# COEXPIX_connectors_schematics.net
KiCad netlist of a schematic drawn in Altium Designer
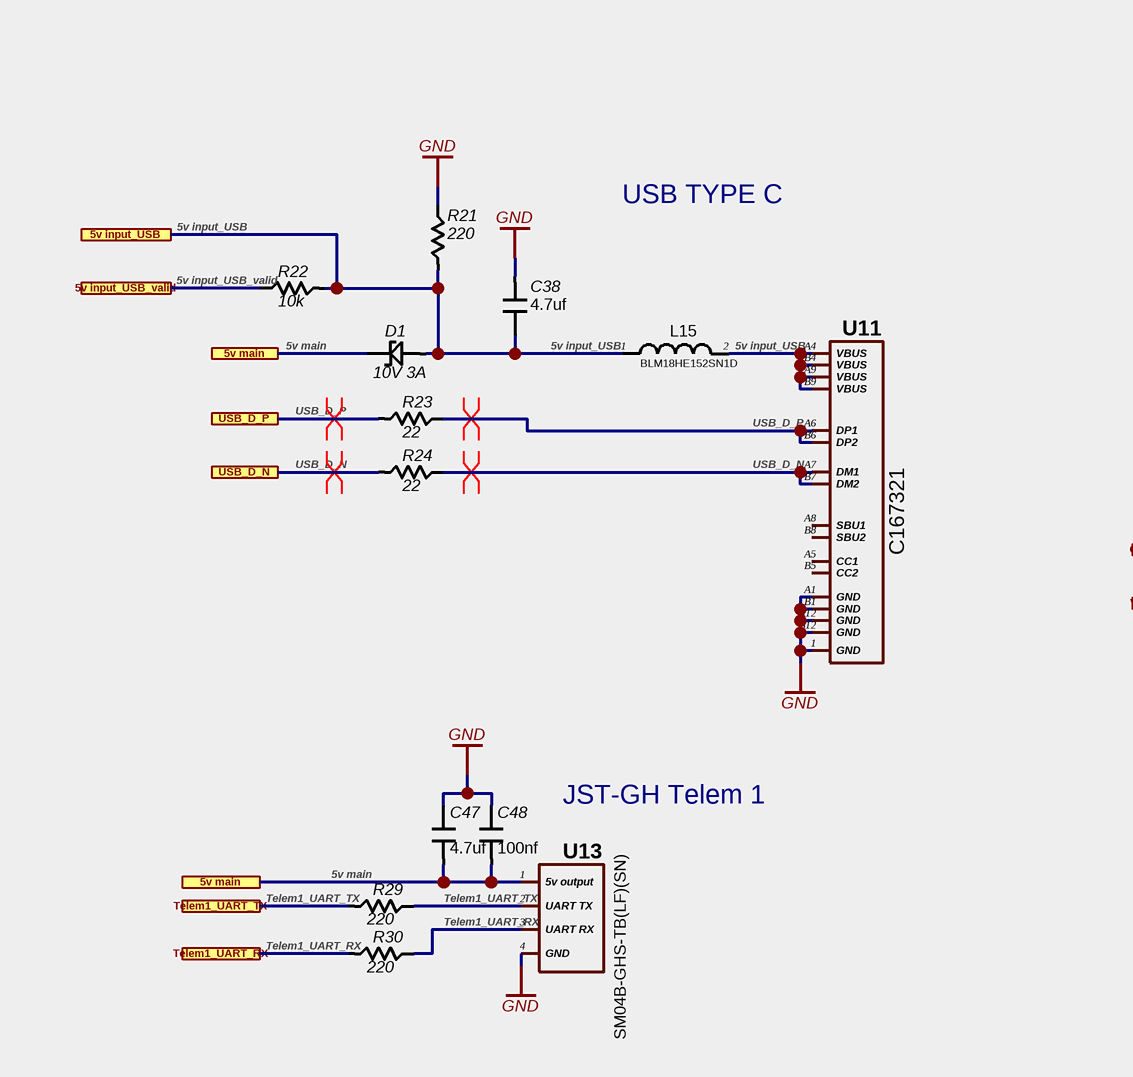
[diagram p0: COEXPIX connectors schematics.SchDoc, top left]
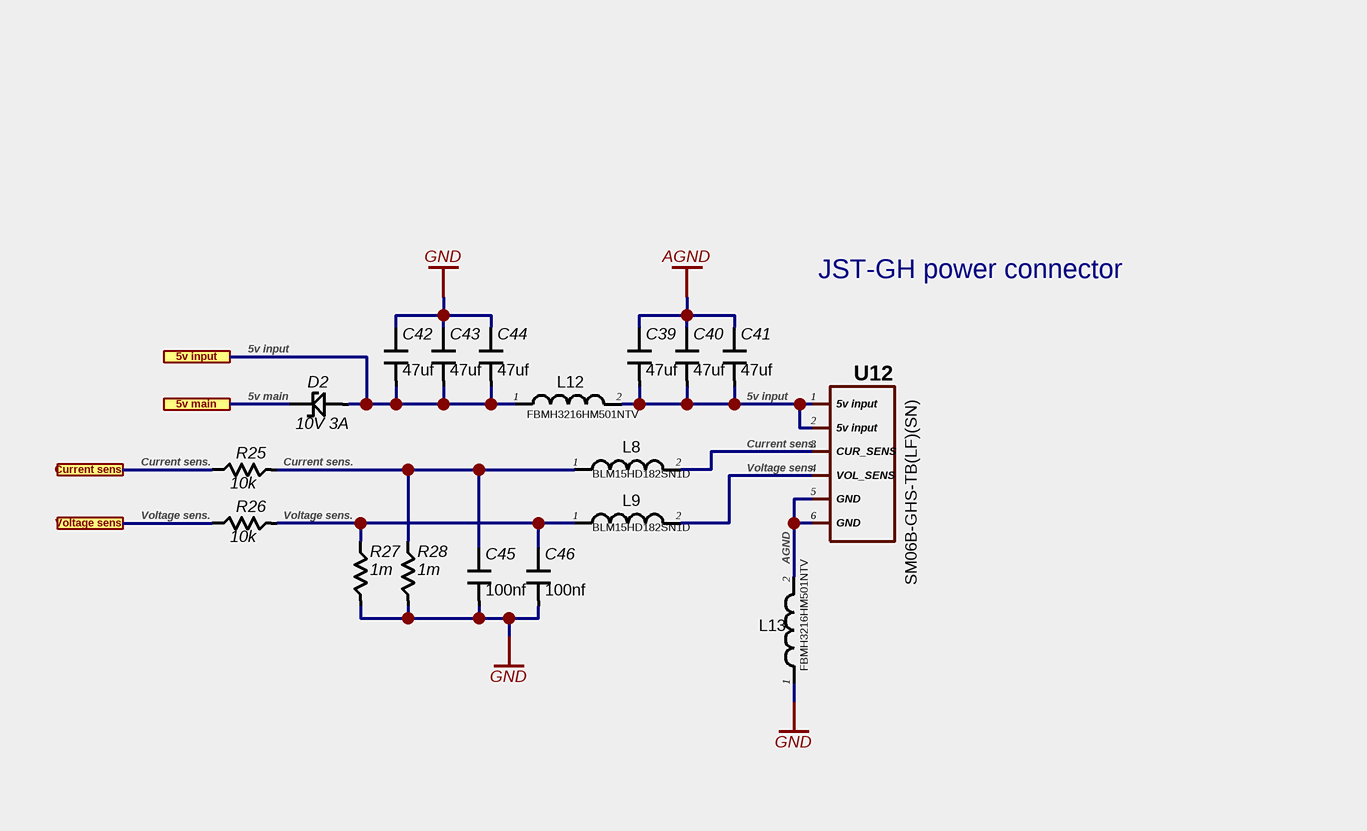
[diagram p1: COEXPIX connectors schematics.SchDoc, top right]
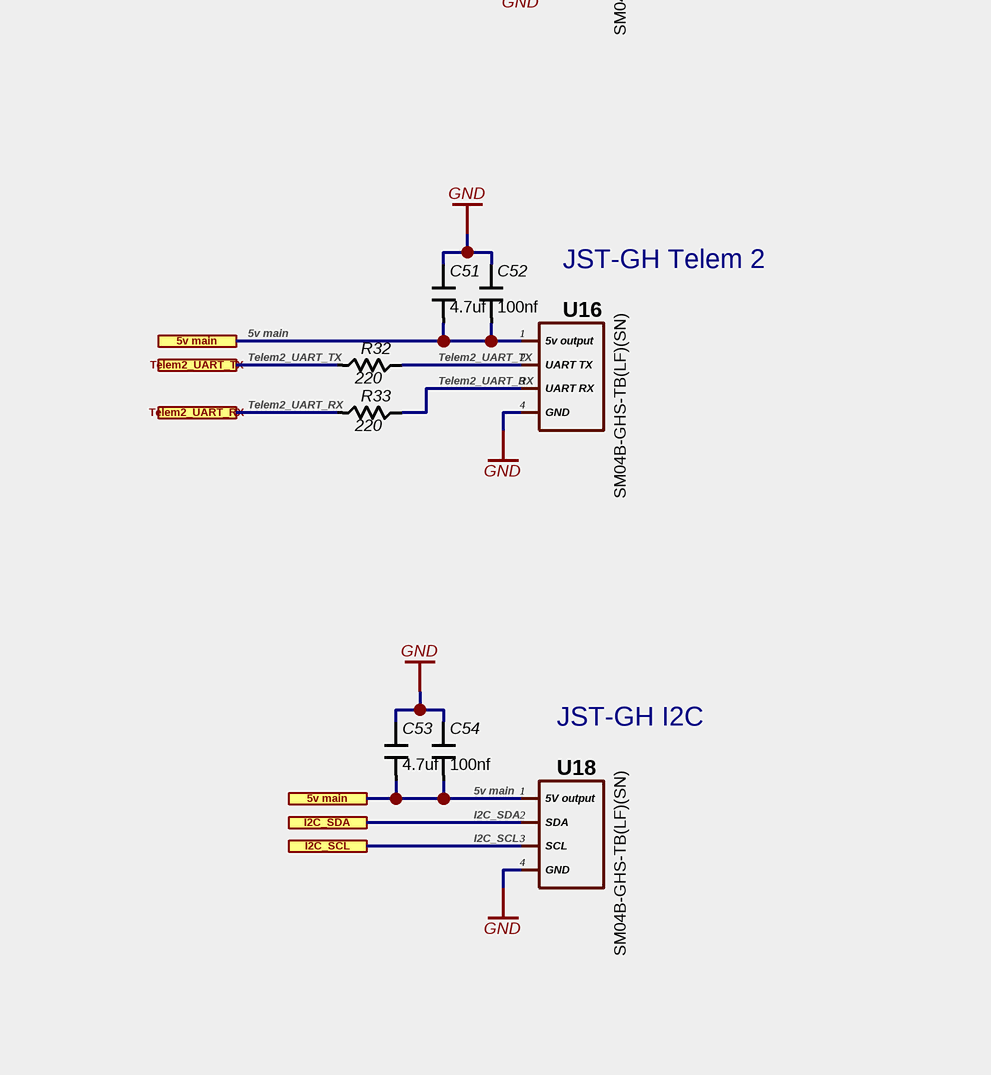
[diagram p2: COEXPIX connectors schematics.SchDoc, bottom left]
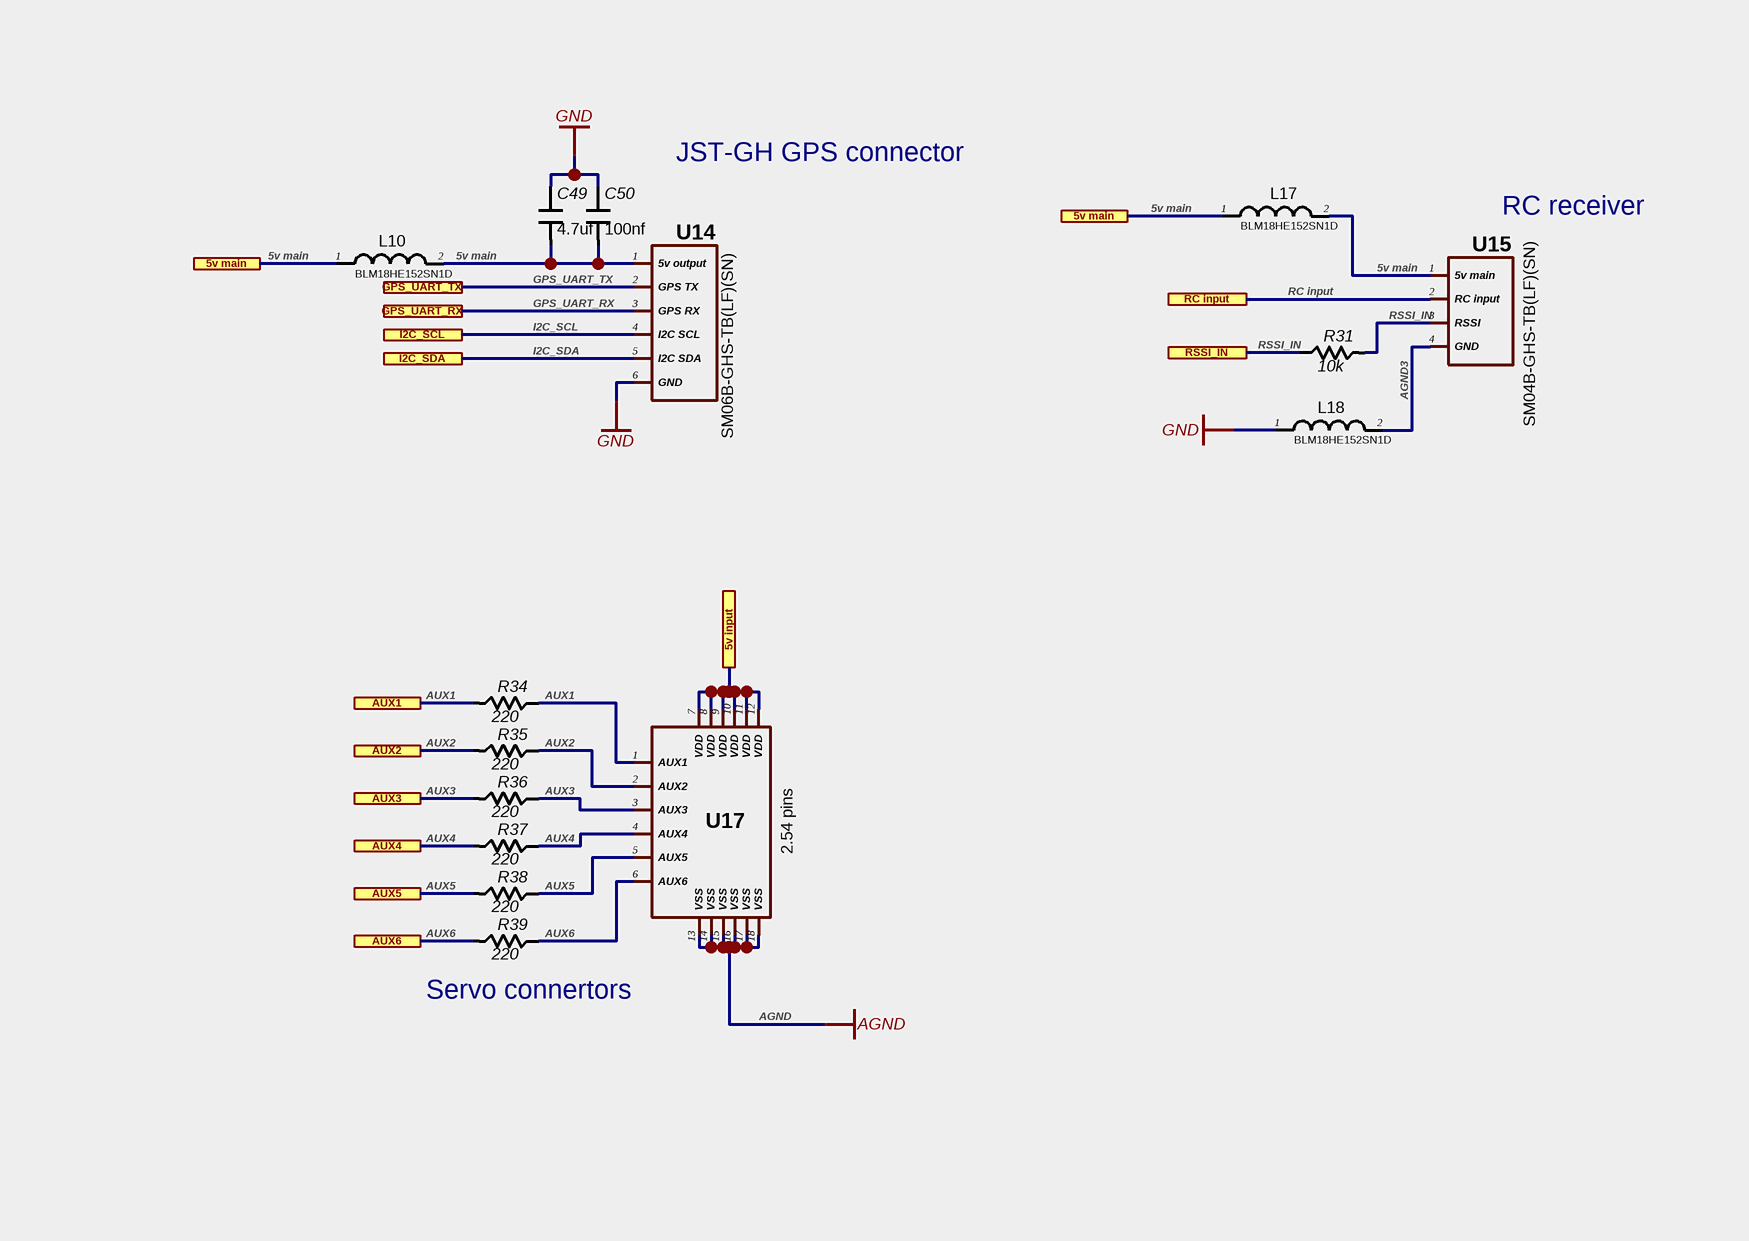
[diagram p3: COEXPIX connectors schematics.SchDoc, bottom right]

(export (version "E")
  (design (tool "Eeschema 10.0.6"))
  (components
    (comp (ref "C38")
      (value "4.7uf")
      (footprint "Capasitor 0402")
      (description "4.7uF ±20% 6.3V X5R 0402 Multilayer Ceramic Capacitor")
      (fields (field (name "PART NUMBER") "JMK105BBJ475MV-F") (field (name "MANUFACTURER") "Taiyo Yuden"))
      (libsource (lib "Schematic symbols library") (part "Capacitor MLCC"))
    )
    (comp (ref "C39")
      (value "47uf")
      (footprint "Capasitor 0603")
      (description "Multilayer Ceramic Capacitors MLCC - SMD/SMT 47uF 6.3V 0603")
      (fields (field (name "PART NUMBER") "GRM188R60J476ME15D") (field (name "MANUFACTURER") "Murata"))
      (libsource (lib "Schematic symbols library") (part "Capacitor MLCC"))
    )
    (comp (ref "C40")
      (value "47uf")
      (footprint "Capasitor 0603")
      (description "Multilayer Ceramic Capacitors MLCC - SMD/SMT 47uF 6.3V 0603")
      (fields (field (name "PART NUMBER") "GRM188R60J476ME15D") (field (name "MANUFACTURER") "Murata"))
      (libsource (lib "Schematic symbols library") (part "Capacitor MLCC"))
    )
    (comp (ref "C41")
      (value "47uf")
      (footprint "Capasitor 0603")
      (description "Multilayer Ceramic Capacitors MLCC - SMD/SMT 47uF 6.3V 0603")
      (fields (field (name "PART NUMBER") "GRM188R60J476ME15D") (field (name "MANUFACTURER") "Murata"))
      (libsource (lib "Schematic symbols library") (part "Capacitor MLCC"))
    )
    (comp (ref "C42")
      (value "47uf")
      (footprint "Capasitor 0603")
      (description "Multilayer Ceramic Capacitors MLCC - SMD/SMT 47uF 6.3V 0603")
      (fields (field (name "PART NUMBER") "GRM188R60J476ME15D") (field (name "MANUFACTURER") "Murata"))
      (libsource (lib "Schematic symbols library") (part "Capacitor MLCC"))
    )
    (comp (ref "C43")
      (value "47uf")
      (footprint "Capasitor 0603")
      (description "Multilayer Ceramic Capacitors MLCC - SMD/SMT 47uF 6.3V 0603")
      (fields (field (name "PART NUMBER") "GRM188R60J476ME15D") (field (name "MANUFACTURER") "Murata"))
      (libsource (lib "Schematic symbols library") (part "Capacitor MLCC"))
    )
    (comp (ref "C44")
      (value "47uf")
      (footprint "Capasitor 0603")
      (description "Multilayer Ceramic Capacitors MLCC - SMD/SMT 47uF 6.3V 0603")
      (fields (field (name "PART NUMBER") "GRM188R60J476ME15D") (field (name "MANUFACTURER") "Murata"))
      (libsource (lib "Schematic symbols library") (part "Capacitor MLCC"))
    )
    (comp (ref "C45")
      (value "100nf")
      (footprint "Capasitor 0402")
      (description "Multilayer Ceramic Capacitors MLCC - SMD/SMT 100nF 16V 0402")
      (fields (field (name "PART NUMBER") "CC0402KRX7R7BB104") (field (name "MANUFACTURER") "YAGEO"))
      (libsource (lib "Schematic symbols library") (part "Capacitor MLCC"))
    )
    (comp (ref "C46")
      (value "100nf")
      (footprint "Capasitor 0402")
      (description "Multilayer Ceramic Capacitors MLCC - SMD/SMT 100nF 16V 0402")
      (fields (field (name "PART NUMBER") "CC0402KRX7R7BB104") (field (name "MANUFACTURER") "YAGEO"))
      (libsource (lib "Schematic symbols library") (part "Capacitor MLCC"))
    )
    (comp (ref "C47")
      (value "4.7uf")
      (footprint "Capasitor 0402")
      (description "4.7uF ±20% 6.3V X5R 0402 Multilayer Ceramic Capacitor")
      (fields (field (name "PART NUMBER") "JMK105BBJ475MV-F") (field (name "MANUFACTURER") "Taiyo Yuden"))
      (libsource (lib "Schematic symbols library") (part "Capacitor MLCC"))
    )
    (comp (ref "C48")
      (value "100nf")
      (footprint "Capasitor 0402")
      (description "Multilayer Ceramic Capacitors MLCC - SMD/SMT 100nF 16V 0402")
      (fields (field (name "PART NUMBER") "CC0402KRX7R7BB104") (field (name "MANUFACTURER") "YAGEO"))
      (libsource (lib "Schematic symbols library") (part "Capacitor MLCC"))
    )
    (comp (ref "C49")
      (value "4.7uf")
      (footprint "Capasitor 0402")
      (description "4.7uF ±20% 6.3V X5R 0402 Multilayer Ceramic Capacitor")
      (fields (field (name "PART NUMBER") "JMK105BBJ475MV-F") (field (name "MANUFACTURER") "Taiyo Yuden"))
      (libsource (lib "Schematic symbols library") (part "Capacitor MLCC"))
    )
    (comp (ref "C50")
      (value "100nf")
      (footprint "Capasitor 0402")
      (description "Multilayer Ceramic Capacitors MLCC - SMD/SMT 100nF 16V 0402")
      (fields (field (name "PART NUMBER") "CC0402KRX7R7BB104") (field (name "MANUFACTURER") "YAGEO"))
      (libsource (lib "Schematic symbols library") (part "Capacitor MLCC"))
    )
    (comp (ref "C51")
      (value "4.7uf")
      (footprint "Capasitor 0402")
      (description "4.7uF ±20% 6.3V X5R 0402 Multilayer Ceramic Capacitor")
      (fields (field (name "PART NUMBER") "JMK105BBJ475MV-F") (field (name "MANUFACTURER") "Taiyo Yuden"))
      (libsource (lib "Schematic symbols library") (part "Capacitor MLCC"))
    )
    (comp (ref "C52")
      (value "100nf")
      (footprint "Capasitor 0402")
      (description "Multilayer Ceramic Capacitors MLCC - SMD/SMT 100nF 16V 0402")
      (fields (field (name "PART NUMBER") "CC0402KRX7R7BB104") (field (name "MANUFACTURER") "YAGEO"))
      (libsource (lib "Schematic symbols library") (part "Capacitor MLCC"))
    )
    (comp (ref "C53")
      (value "4.7uf")
      (footprint "Capasitor 0402")
      (description "4.7uF ±20% 6.3V X5R 0402 Multilayer Ceramic Capacitor")
      (fields (field (name "PART NUMBER") "JMK105BBJ475MV-F") (field (name "MANUFACTURER") "Taiyo Yuden"))
      (libsource (lib "Schematic symbols library") (part "Capacitor MLCC"))
    )
    (comp (ref "C54")
      (value "100nf")
      (footprint "Capasitor 0402")
      (description "Multilayer Ceramic Capacitors MLCC - SMD/SMT 100nF 16V 0402")
      (fields (field (name "PART NUMBER") "CC0402KRX7R7BB104") (field (name "MANUFACTURER") "YAGEO"))
      (libsource (lib "Schematic symbols library") (part "Capacitor MLCC"))
    )
    (comp (ref "D1")
      (value "10V 3A")
      (footprint "SOD-323F")
      (description "10V 3A 580mV @ 1A SOD-323 Schottky Barrier Diode")
      (fields (field (name "PART NUMBER") "BAT60JFILM") (field (name "MANUFACTURER") "STMicroelectronics"))
      (libsource (lib "Schematic symbols library") (part "Schottky barrier diode"))
    )
    (comp (ref "D2")
      (value "10V 3A")
      (footprint "SOD-323F")
      (description "10V 3A 580mV @ 1A SOD-323 Schottky Barrier Diode")
      (fields (field (name "PART NUMBER") "BAT60JFILM") (field (name "MANUFACTURER") "STMicroelectronics"))
      (libsource (lib "Schematic symbols library") (part "Schottky barrier diode"))
    )
    (comp (ref "L8")
      (value "BLM15HD182SN1D")
      (footprint "Ferrite bead 0402")
      (description "Beads 0402")
      (fields (field (name "MANUFACTURER") "Murata Electronics"))
      (libsource (lib "Schematic symbols library") (part "FB / Inductor"))
    )
    (comp (ref "L9")
      (value "BLM15HD182SN1D")
      (footprint "Ferrite bead 0402")
      (description "Beads 0402")
      (fields (field (name "MANUFACTURER") "Murata Electronics"))
      (libsource (lib "Schematic symbols library") (part "FB / Inductor"))
    )
    (comp (ref "L10")
      (value "BLM18HE152SN1D")
      (footprint "Ferrite bead 0603")
      (description "1.5kΩ @ 100MHz 500mA 1 500mΩ 0603 Ferrite Bead")
      (fields (field (name "MANUFACTURER") "Murata"))
      (libsource (lib "Schematic symbols library") (part "FB / Inductor"))
    )
    (comp (ref "L12")
      (value "FBMH3216HM501NTV")
      (footprint "FERRITE BEAD 1206")
      (description "500Ω @ 100MHz 2A 1 70mΩ 1206 Ferrite Bead")
      (fields (field (name "MANUFACTURER") "Taiyo Yuden"))
      (libsource (lib "Schematic symbols library") (part "FB / Inductor"))
    )
    (comp (ref "L13")
      (value "FBMH3216HM501NTV")
      (footprint "FERRITE BEAD 1206")
      (description "500Ω @ 100MHz 2A 1 70mΩ 1206 Ferrite Bead")
      (fields (field (name "MANUFACTURER") "Taiyo Yuden"))
      (libsource (lib "Schematic symbols library") (part "FB / Inductor"))
    )
    (comp (ref "L15")
      (value "BLM18HE152SN1D")
      (footprint "Ferrite bead 0603")
      (description "1.5kΩ @ 100MHz 500mA 1 500mΩ 0603 Ferrite Bead")
      (fields (field (name "MANUFACTURER") "Murata"))
      (libsource (lib "Schematic symbols library") (part "FB / Inductor"))
    )
    (comp (ref "L17")
      (value "BLM18HE152SN1D")
      (footprint "Ferrite bead 0603")
      (description "1.5kΩ @ 100MHz 500mA 1 500mΩ 0603 Ferrite Bead")
      (fields (field (name "MANUFACTURER") "Murata"))
      (libsource (lib "Schematic symbols library") (part "FB / Inductor"))
    )
    (comp (ref "L18")
      (value "BLM18HE152SN1D")
      (footprint "Ferrite bead 0603")
      (description "1.5kΩ @ 100MHz 500mA 1 500mΩ 0603 Ferrite Bead")
      (fields (field (name "MANUFACTURER") "Murata"))
      (libsource (lib "Schematic symbols library") (part "FB / Inductor"))
    )
    (comp (ref "R21")
      (value "220")
      (footprint "Resistor 0402")
      (description "Chip Resistor - Surface Mount 220Ohms ±1% 1/16W 040")
      (fields (field (name "PART NUMBER") "0402WGF2200TCE") (field (name "MANUFACTURER") "Uniroyal Elec"))
      (libsource (lib "Schematic symbols library") (part "Resistor"))
    )
    (comp (ref "R22")
      (value "10k")
      (footprint "Resistor 0402")
      (description "Chip Resistor - Surface Mount 10KOhms ±1% 1/16W 0402")
      (fields (field (name "PART NUMBER") "RC0402FR-0710KL") (field (name "MANUFACTURER") "YAGEO"))
      (libsource (lib "Schematic symbols library") (part "Resistor"))
    )
    (comp (ref "R23")
      (value "22")
      (footprint "Resistor 0402")
      (description "Chip Resistor - Surface Mount 22Ohms ±1% 1/16W 0402")
      (fields (field (name "PART NUMBER") "RC0402FR-0722RL") (field (name "MANUFACTURER") "YAGEO"))
      (libsource (lib "Schematic symbols library") (part "Resistor"))
    )
    (comp (ref "R24")
      (value "22")
      (footprint "Resistor 0402")
      (description "Chip Resistor - Surface Mount 22Ohms ±1% 1/16W 0402")
      (fields (field (name "PART NUMBER") "RC0402FR-0722RL") (field (name "MANUFACTURER") "YAGEO"))
      (libsource (lib "Schematic symbols library") (part "Resistor"))
    )
    (comp (ref "R25")
      (value "10k")
      (footprint "Resistor 0402")
      (description "Chip Resistor - Surface Mount 10KOhms ±1% 1/16W 0402")
      (fields (field (name "PART NUMBER") "RC0402FR-0710KL") (field (name "MANUFACTURER") "YAGEO"))
      (libsource (lib "Schematic symbols library") (part "Resistor"))
    )
    (comp (ref "R26")
      (value "10k")
      (footprint "Resistor 0402")
      (description "Chip Resistor - Surface Mount 10KOhms ±1% 1/16W 0402")
      (fields (field (name "PART NUMBER") "RC0402FR-0710KL") (field (name "MANUFACTURER") "YAGEO"))
      (libsource (lib "Schematic symbols library") (part "Resistor"))
    )
    (comp (ref "R27")
      (value "1m")
      (footprint "Resistor 0402")
      (description "1M ±1% 1/16W ±100ppm/°C 0402 Chip Resistor")
      (fields (field (name "PART NUMBER") "RC0402FR-071ML") (field (name "MANUFACTURER") "YAGEO"))
      (libsource (lib "Schematic symbols library") (part "Resistor"))
    )
    (comp (ref "R28")
      (value "1m")
      (footprint "Resistor 0402")
      (description "1M ±1% 1/16W ±100ppm/°C 0402 Chip Resistor")
      (fields (field (name "PART NUMBER") "RC0402FR-071ML") (field (name "MANUFACTURER") "YAGEO"))
      (libsource (lib "Schematic symbols library") (part "Resistor"))
    )
    (comp (ref "R29")
      (value "220")
      (footprint "Resistor 0402")
      (description "Chip Resistor - Surface Mount 220Ohms ±1% 1/16W 040")
      (fields (field (name "PART NUMBER") "0402WGF2200TCE") (field (name "MANUFACTURER") "Uniroyal Elec"))
      (libsource (lib "Schematic symbols library") (part "Resistor"))
    )
    (comp (ref "R30")
      (value "220")
      (footprint "Resistor 0402")
      (description "Chip Resistor - Surface Mount 220Ohms ±1% 1/16W 040")
      (fields (field (name "PART NUMBER") "0402WGF2200TCE") (field (name "MANUFACTURER") "Uniroyal Elec"))
      (libsource (lib "Schematic symbols library") (part "Resistor"))
    )
    (comp (ref "R31")
      (value "10k")
      (footprint "Resistor 0402")
      (description "Chip Resistor - Surface Mount 10KOhms ±1% 1/16W 0402")
      (fields (field (name "PART NUMBER") "RC0402FR-0710KL") (field (name "MANUFACTURER") "YAGEO"))
      (libsource (lib "Schematic symbols library") (part "Resistor"))
    )
    (comp (ref "R32")
      (value "220")
      (footprint "Resistor 0402")
      (description "Chip Resistor - Surface Mount 220Ohms ±1% 1/16W 040")
      (fields (field (name "PART NUMBER") "0402WGF2200TCE") (field (name "MANUFACTURER") "Uniroyal Elec"))
      (libsource (lib "Schematic symbols library") (part "Resistor"))
    )
    (comp (ref "R33")
      (value "220")
      (footprint "Resistor 0402")
      (description "Chip Resistor - Surface Mount 220Ohms ±1% 1/16W 040")
      (fields (field (name "PART NUMBER") "0402WGF2200TCE") (field (name "MANUFACTURER") "Uniroyal Elec"))
      (libsource (lib "Schematic symbols library") (part "Resistor"))
    )
    (comp (ref "R34")
      (value "220")
      (footprint "Resistor 0402")
      (description "Chip Resistor - Surface Mount 220Ohms ±1% 1/16W 040")
      (fields (field (name "PART NUMBER") "0402WGF2200TCE") (field (name "MANUFACTURER") "Uniroyal Elec"))
      (libsource (lib "Schematic symbols library") (part "Resistor"))
    )
    (comp (ref "R35")
      (value "220")
      (footprint "Resistor 0402")
      (description "Chip Resistor - Surface Mount 220Ohms ±1% 1/16W 040")
      (fields (field (name "PART NUMBER") "0402WGF2200TCE") (field (name "MANUFACTURER") "Uniroyal Elec"))
      (libsource (lib "Schematic symbols library") (part "Resistor"))
    )
    (comp (ref "R36")
      (value "220")
      (footprint "Resistor 0402")
      (description "Chip Resistor - Surface Mount 220Ohms ±1% 1/16W 040")
      (fields (field (name "PART NUMBER") "0402WGF2200TCE") (field (name "MANUFACTURER") "Uniroyal Elec"))
      (libsource (lib "Schematic symbols library") (part "Resistor"))
    )
    (comp (ref "R37")
      (value "220")
      (footprint "Resistor 0402")
      (description "Chip Resistor - Surface Mount 220Ohms ±1% 1/16W 040")
      (fields (field (name "PART NUMBER") "0402WGF2200TCE") (field (name "MANUFACTURER") "Uniroyal Elec"))
      (libsource (lib "Schematic symbols library") (part "Resistor"))
    )
    (comp (ref "R38")
      (value "220")
      (footprint "Resistor 0402")
      (description "Chip Resistor - Surface Mount 220Ohms ±1% 1/16W 040")
      (fields (field (name "PART NUMBER") "0402WGF2200TCE") (field (name "MANUFACTURER") "Uniroyal Elec"))
      (libsource (lib "Schematic symbols library") (part "Resistor"))
    )
    (comp (ref "R39")
      (value "220")
      (footprint "Resistor 0402")
      (description "Chip Resistor - Surface Mount 220Ohms ±1% 1/16W 040")
      (fields (field (name "PART NUMBER") "0402WGF2200TCE") (field (name "MANUFACTURER") "Uniroyal Elec"))
      (libsource (lib "Schematic symbols library") (part "Resistor"))
    )
    (comp (ref "U11")
      (value "C167321")
      (footprint "USB TYPE C")
      (description "USB - Type C Receptacle 12 SMD USB Connector")
      (fields (field (name "MANUFACTURER") "Jing Extension of the Electronic Co."))
      (libsource (lib "Schematic symbols library") (part "USB type C"))
    )
    (comp (ref "U12")
      (value "SM06B-GHS-TB(LF)(SN)")
      (footprint "JST-GH 6 PIN")
      (description "Wire To Board / Wire To Wire Connector SMD")
      (fields (field (name "MANUFACTURER") "JST Sales America"))
      (libsource (lib "Schematic symbols library") (part "JST-GH 6"))
    )
    (comp (ref "U13")
      (value "SM04B-GHS-TB(LF)(SN)")
      (footprint "JST-GH 4 pin")
      (fields (field (name "MANUFACTURER") "JST Sales America"))
      (libsource (lib "") (part "JST-GH 4_1"))
    )
    (comp (ref "U14")
      (value "SM06B-GHS-TB(LF)(SN)")
      (footprint "JST-GH 6 PIN")
      (description "Wire To Board / Wire To Wire Connector SMD")
      (fields (field (name "MANUFACTURER") "JST Sales America"))
      (libsource (lib "Schematic symbols library") (part "JST-GH 6"))
    )
    (comp (ref "U15")
      (value "SM04B-GHS-TB(LF)(SN)")
      (footprint "JST-GH 4 pin")
      (description "Wire To Board / Wire To Wire Connector socket P=1.25mm")
      (fields (field (name "MANUFACTURER") "JST Sales America"))
      (libsource (lib "Schematic symbols library") (part "JST-GH 4"))
    )
    (comp (ref "U16")
      (value "SM04B-GHS-TB(LF)(SN)")
      (footprint "JST-GH 4 pin")
      (description "Wire To Board / Wire To Wire Connector socket P=1.25mm")
      (fields (field (name "MANUFACTURER") "JST Sales America"))
      (libsource (lib "Schematic symbols library") (part "JST-GH 4"))
    )
    (comp (ref "U17")
      (value "2.54 pins")
      (footprint "3x6 PX4 servo array")
      (fields (field (name "PART NUMBER") "2.54 pins array"))
      (libsource (lib "Schematic symbols library") (part "3x6 dupont pins"))
    )
    (comp (ref "U18")
      (value "SM04B-GHS-TB(LF)(SN)")
      (footprint "JST-GH 4 pin")
      (description "Wire To Board / Wire To Wire Connector socket P=1.25mm")
      (fields (field (name "MANUFACTURER") "JST Sales America"))
      (libsource (lib "Schematic symbols library") (part "JST-GH 4"))
    )
  )
  (nets
    (net (code "1") (name "/5v input") (class "Default")
      (node (ref "C39") (pin "2") (pinfunction "2_2") (pintype "passive"))
      (node (ref "C40") (pin "2") (pinfunction "2_2") (pintype "passive"))
      (node (ref "C41") (pin "2") (pinfunction "2_2") (pintype "passive"))
      (node (ref "C42") (pin "2") (pinfunction "2_2") (pintype "passive"))
      (node (ref "C43") (pin "2") (pinfunction "2_2") (pintype "passive"))
      (node (ref "C44") (pin "2") (pinfunction "2_2") (pintype "passive"))
      (node (ref "D2") (pin "2") (pinfunction "2_2") (pintype "passive"))
      (node (ref "L12") (pin "1") (pintype "power_in"))
      (node (ref "L12") (pin "2") (pintype "power_in"))
      (node (ref "U12") (pin "1") (pinfunction "5v_input_1") (pintype "power_in"))
      (node (ref "U12") (pin "2") (pinfunction "5v_input_2") (pintype "power_in"))
      (node (ref "U17") (pin "10") (pinfunction "VDD_10") (pintype "power_in"))
      (node (ref "U17") (pin "11") (pinfunction "VDD_11") (pintype "power_in"))
      (node (ref "U17") (pin "12") (pinfunction "VDD_12") (pintype "power_in"))
      (node (ref "U17") (pin "7") (pinfunction "VDD_7") (pintype "power_in"))
      (node (ref "U17") (pin "8") (pinfunction "VDD_8") (pintype "power_in"))
      (node (ref "U17") (pin "9") (pinfunction "VDD_9") (pintype "power_in"))
    )
    (net (code "2") (name "/5v input_USB") (class "Default")
      (node (ref "C38") (pin "1") (pinfunction "1_1") (pintype "passive"))
      (node (ref "D1") (pin "2") (pinfunction "2_2") (pintype "passive"))
      (node (ref "L15") (pin "1") (pintype "power_in"))
      (node (ref "L15") (pin "2") (pintype "power_in"))
      (node (ref "R21") (pin "2") (pinfunction "2_2") (pintype "passive"))
      (node (ref "R22") (pin "2") (pinfunction "2_2") (pintype "passive"))
      (node (ref "U11") (pin "A4") (pinfunction "VBUS_A4") (pintype "power_in"))
      (node (ref "U11") (pin "A9") (pinfunction "VBUS_A9") (pintype "power_in"))
      (node (ref "U11") (pin "B4") (pinfunction "VBUS_B4") (pintype "power_in"))
      (node (ref "U11") (pin "B9") (pinfunction "VBUS_B9") (pintype "power_in"))
    )
    (net (code "3") (name "/5v input_USB_valid") (class "Default")
      (node (ref "R22") (pin "1") (pinfunction "1_1") (pintype "passive"))
    )
    (net (code "4") (name "/5v main") (class "Default")
      (node (ref "C47") (pin "2") (pinfunction "2_2") (pintype "passive"))
      (node (ref "C48") (pin "2") (pinfunction "2_2") (pintype "passive"))
      (node (ref "C49") (pin "2") (pinfunction "2_2") (pintype "passive"))
      (node (ref "C50") (pin "2") (pinfunction "2_2") (pintype "passive"))
      (node (ref "C51") (pin "2") (pinfunction "2_2") (pintype "passive"))
      (node (ref "C52") (pin "2") (pinfunction "2_2") (pintype "passive"))
      (node (ref "C53") (pin "2") (pinfunction "2_2") (pintype "passive"))
      (node (ref "C54") (pin "2") (pinfunction "2_2") (pintype "passive"))
      (node (ref "D1") (pin "1") (pinfunction "1_1") (pintype "passive"))
      (node (ref "D2") (pin "1") (pinfunction "1_1") (pintype "passive"))
      (node (ref "L10") (pin "1") (pintype "power_in"))
      (node (ref "L10") (pin "2") (pintype "power_in"))
      (node (ref "L17") (pin "1") (pintype "power_in"))
      (node (ref "L17") (pin "2") (pintype "power_in"))
      (node (ref "U13") (pin "1") (pinfunction "5v_output_1") (pintype "power_in"))
      (node (ref "U14") (pin "1") (pinfunction "5v_input_1") (pintype "power_in"))
      (node (ref "U15") (pin "1") (pinfunction "5V_output_1") (pintype "power_in"))
      (node (ref "U16") (pin "1") (pinfunction "5V_output_1") (pintype "power_in"))
      (node (ref "U18") (pin "1") (pinfunction "5V_output_1") (pintype "power_in"))
    )
    (net (code "5") (name "/AGND3") (class "Default")
      (node (ref "L18") (pin "2") (pintype "power_in"))
      (node (ref "U15") (pin "4") (pinfunction "GND_4") (pintype "power_in"))
    )
    (net (code "6") (name "/AUX1") (class "Default")
      (node (ref "R34") (pin "1") (pinfunction "1_1") (pintype "passive"))
      (node (ref "R34") (pin "2") (pinfunction "2_2") (pintype "passive"))
      (node (ref "U17") (pin "1") (pinfunction "AUX1_1") (pintype "power_in"))
    )
    (net (code "7") (name "/AUX2") (class "Default")
      (node (ref "R35") (pin "1") (pinfunction "1_1") (pintype "passive"))
      (node (ref "R35") (pin "2") (pinfunction "2_2") (pintype "passive"))
      (node (ref "U17") (pin "2") (pinfunction "AUX2_2") (pintype "power_in"))
    )
    (net (code "8") (name "/AUX3") (class "Default")
      (node (ref "R36") (pin "1") (pinfunction "1_1") (pintype "passive"))
      (node (ref "R36") (pin "2") (pinfunction "2_2") (pintype "passive"))
      (node (ref "U17") (pin "3") (pinfunction "AUX3_3") (pintype "power_in"))
    )
    (net (code "9") (name "/AUX4") (class "Default")
      (node (ref "R37") (pin "1") (pinfunction "1_1") (pintype "passive"))
      (node (ref "R37") (pin "2") (pinfunction "2_2") (pintype "passive"))
      (node (ref "U17") (pin "4") (pinfunction "AUX4_4") (pintype "power_in"))
    )
    (net (code "10") (name "/AUX5") (class "Default")
      (node (ref "R38") (pin "1") (pinfunction "1_1") (pintype "passive"))
      (node (ref "R38") (pin "2") (pinfunction "2_2") (pintype "passive"))
      (node (ref "U17") (pin "5") (pinfunction "AUX5_5") (pintype "power_in"))
    )
    (net (code "11") (name "/AUX6") (class "Default")
      (node (ref "R39") (pin "1") (pinfunction "1_1") (pintype "passive"))
      (node (ref "R39") (pin "2") (pinfunction "2_2") (pintype "passive"))
      (node (ref "U17") (pin "6") (pinfunction "AUX6_6") (pintype "power_in"))
    )
    (net (code "12") (name "/Current sens.") (class "Default")
      (node (ref "C45") (pin "1") (pinfunction "1_1") (pintype "passive"))
      (node (ref "L8") (pin "1") (pintype "power_in"))
      (node (ref "L8") (pin "2") (pintype "power_in"))
      (node (ref "R25") (pin "1") (pinfunction "1_1") (pintype "passive"))
      (node (ref "R25") (pin "2") (pinfunction "2_2") (pintype "passive"))
      (node (ref "R28") (pin "1") (pinfunction "1_1") (pintype "passive"))
      (node (ref "U12") (pin "3") (pinfunction "CUR_SENS_3") (pintype "power_in"))
    )
    (net (code "13") (name "/GPS_UART_RX") (class "Default")
      (node (ref "U14") (pin "3") (pinfunction "CUR_SENS_3") (pintype "power_in"))
    )
    (net (code "14") (name "/GPS_UART_TX") (class "Default")
      (node (ref "U14") (pin "2") (pinfunction "5v_input_2") (pintype "power_in"))
    )
    (net (code "15") (name "/I2C_SCL") (class "Default")
      (node (ref "U14") (pin "4") (pinfunction "VOL_SENS_4") (pintype "power_in"))
      (node (ref "U18") (pin "3") (pinfunction "SCL_3") (pintype "power_in"))
    )
    (net (code "16") (name "/I2C_SDA") (class "Default")
      (node (ref "U14") (pin "5") (pinfunction "GND_5") (pintype "power_in"))
      (node (ref "U18") (pin "2") (pinfunction "SDA_2") (pintype "power_in"))
    )
    (net (code "17") (name "/RC input") (class "Default")
      (node (ref "U15") (pin "2") (pinfunction "SDA_2") (pintype "power_in"))
    )
    (net (code "18") (name "/RSSI_IN") (class "Default")
      (node (ref "R31") (pin "1") (pinfunction "1_1") (pintype "passive"))
      (node (ref "R31") (pin "2") (pinfunction "2_2") (pintype "passive"))
      (node (ref "U15") (pin "3") (pinfunction "SCL_3") (pintype "power_in"))
    )
    (net (code "19") (name "/Telem1_UART_RX") (class "Default")
      (node (ref "R30") (pin "1") (pinfunction "1_1") (pintype "passive"))
      (node (ref "R30") (pin "2") (pinfunction "2_2") (pintype "passive"))
      (node (ref "U13") (pin "3") (pinfunction "UART_RX_3") (pintype "power_in"))
    )
    (net (code "20") (name "/Telem1_UART_TX") (class "Default")
      (node (ref "R29") (pin "1") (pinfunction "1_1") (pintype "passive"))
      (node (ref "R29") (pin "2") (pinfunction "2_2") (pintype "passive"))
      (node (ref "U13") (pin "2") (pinfunction "UART_TX_2") (pintype "power_in"))
    )
    (net (code "21") (name "/Telem2_UART_RX") (class "Default")
      (node (ref "R33") (pin "1") (pinfunction "1_1") (pintype "passive"))
      (node (ref "R33") (pin "2") (pinfunction "2_2") (pintype "passive"))
      (node (ref "U16") (pin "3") (pinfunction "SCL_3") (pintype "power_in"))
    )
    (net (code "22") (name "/Telem2_UART_TX") (class "Default")
      (node (ref "R32") (pin "1") (pinfunction "1_1") (pintype "passive"))
      (node (ref "R32") (pin "2") (pinfunction "2_2") (pintype "passive"))
      (node (ref "U16") (pin "2") (pinfunction "SDA_2") (pintype "power_in"))
    )
    (net (code "23") (name "/USB_D_N") (class "Default")
      (node (ref "R24") (pin "1") (pinfunction "1_1") (pintype "passive"))
      (node (ref "R24") (pin "2") (pinfunction "2_2") (pintype "passive"))
      (node (ref "U11") (pin "A7") (pinfunction "DM1_A7") (pintype "power_in"))
      (node (ref "U11") (pin "B7") (pinfunction "DM2_B7") (pintype "power_in"))
    )
    (net (code "24") (name "/USB_D_P") (class "Default")
      (node (ref "R23") (pin "1") (pinfunction "1_1") (pintype "passive"))
      (node (ref "R23") (pin "2") (pinfunction "2_2") (pintype "passive"))
      (node (ref "U11") (pin "A6") (pinfunction "DP1_A6") (pintype "power_in"))
      (node (ref "U11") (pin "B6") (pinfunction "DP2_B6") (pintype "power_in"))
    )
    (net (code "25") (name "/Voltage sens.") (class "Default")
      (node (ref "C46") (pin "1") (pinfunction "1_1") (pintype "passive"))
      (node (ref "L9") (pin "1") (pintype "power_in"))
      (node (ref "L9") (pin "2") (pintype "power_in"))
      (node (ref "R26") (pin "1") (pinfunction "1_1") (pintype "passive"))
      (node (ref "R26") (pin "2") (pinfunction "2_2") (pintype "passive"))
      (node (ref "R27") (pin "1") (pinfunction "1_1") (pintype "passive"))
      (node (ref "U12") (pin "4") (pinfunction "VOL_SENS_4") (pintype "power_in"))
    )
    (net (code "26") (name "AGND") (class "Default")
      (node (ref "C39") (pin "1") (pinfunction "1_1") (pintype "passive"))
      (node (ref "C40") (pin "1") (pinfunction "1_1") (pintype "passive"))
      (node (ref "C41") (pin "1") (pinfunction "1_1") (pintype "passive"))
      (node (ref "L13") (pin "2") (pintype "power_in"))
      (node (ref "U12") (pin "5") (pinfunction "GND_5") (pintype "power_in"))
      (node (ref "U12") (pin "6") (pinfunction "GND_6") (pintype "power_in"))
      (node (ref "U17") (pin "13") (pinfunction "VSS_13") (pintype "power_in"))
      (node (ref "U17") (pin "14") (pinfunction "VSS_14") (pintype "power_in"))
      (node (ref "U17") (pin "15") (pinfunction "VSS_15") (pintype "power_in"))
      (node (ref "U17") (pin "16") (pinfunction "VSS_16") (pintype "power_in"))
      (node (ref "U17") (pin "17") (pinfunction "VSS_17") (pintype "power_in"))
      (node (ref "U17") (pin "18") (pinfunction "VSS_18") (pintype "power_in"))
    )
    (net (code "27") (name "GND") (class "Default")
      (node (ref "C38") (pin "2") (pinfunction "2_2") (pintype "passive"))
      (node (ref "C42") (pin "1") (pinfunction "1_1") (pintype "passive"))
      (node (ref "C43") (pin "1") (pinfunction "1_1") (pintype "passive"))
      (node (ref "C44") (pin "1") (pinfunction "1_1") (pintype "passive"))
      (node (ref "C45") (pin "2") (pinfunction "2_2") (pintype "passive"))
      (node (ref "C46") (pin "2") (pinfunction "2_2") (pintype "passive"))
      (node (ref "C47") (pin "1") (pinfunction "1_1") (pintype "passive"))
      (node (ref "C48") (pin "1") (pinfunction "1_1") (pintype "passive"))
      (node (ref "C49") (pin "1") (pinfunction "1_1") (pintype "passive"))
      (node (ref "C50") (pin "1") (pinfunction "1_1") (pintype "passive"))
      (node (ref "C51") (pin "1") (pinfunction "1_1") (pintype "passive"))
      (node (ref "C52") (pin "1") (pinfunction "1_1") (pintype "passive"))
      (node (ref "C53") (pin "1") (pinfunction "1_1") (pintype "passive"))
      (node (ref "C54") (pin "1") (pinfunction "1_1") (pintype "passive"))
      (node (ref "L13") (pin "1") (pintype "power_in"))
      (node (ref "L18") (pin "1") (pintype "power_in"))
      (node (ref "R21") (pin "1") (pinfunction "1_1") (pintype "passive"))
      (node (ref "R27") (pin "2") (pinfunction "2_2") (pintype "passive"))
      (node (ref "R28") (pin "2") (pinfunction "2_2") (pintype "passive"))
      (node (ref "U11") (pin "1") (pinfunction "GND_1") (pintype "power_in"))
      (node (ref "U11") (pin "A1") (pinfunction "GND_A1") (pintype "power_in"))
      (node (ref "U11") (pin "A12") (pinfunction "GND_A12") (pintype "power_in"))
      (node (ref "U11") (pin "B1") (pinfunction "GND_B1") (pintype "power_in"))
      (node (ref "U11") (pin "B12") (pinfunction "GND_B12") (pintype "power_in"))
      (node (ref "U13") (pin "4") (pinfunction "GND_4") (pintype "power_in"))
      (node (ref "U14") (pin "6") (pinfunction "GND_6") (pintype "power_in"))
      (node (ref "U16") (pin "4") (pinfunction "GND_4") (pintype "power_in"))
      (node (ref "U18") (pin "4") (pinfunction "GND_4") (pintype "power_in"))
    )
    (net (code "28") (name "unconnected-(U11-CC1-PadA5)") (class "Default")
      (node (ref "U11") (pin "A5") (pinfunction "CC1_A5") (pintype "power_in"))
    )
    (net (code "29") (name "unconnected-(U11-CC2-PadB5)") (class "Default")
      (node (ref "U11") (pin "B5") (pinfunction "CC2_B5") (pintype "power_in"))
    )
    (net (code "30") (name "unconnected-(U11-SBU1-PadA8)") (class "Default")
      (node (ref "U11") (pin "A8") (pinfunction "SBU1_A8") (pintype "power_in"))
    )
    (net (code "31") (name "unconnected-(U11-SBU2-PadB8)") (class "Default")
      (node (ref "U11") (pin "B8") (pinfunction "SBU2_B8") (pintype "power_in"))
    )
  )
)
